# zero_board.net
KiCad netlist of a schematic drawn in EAGLE
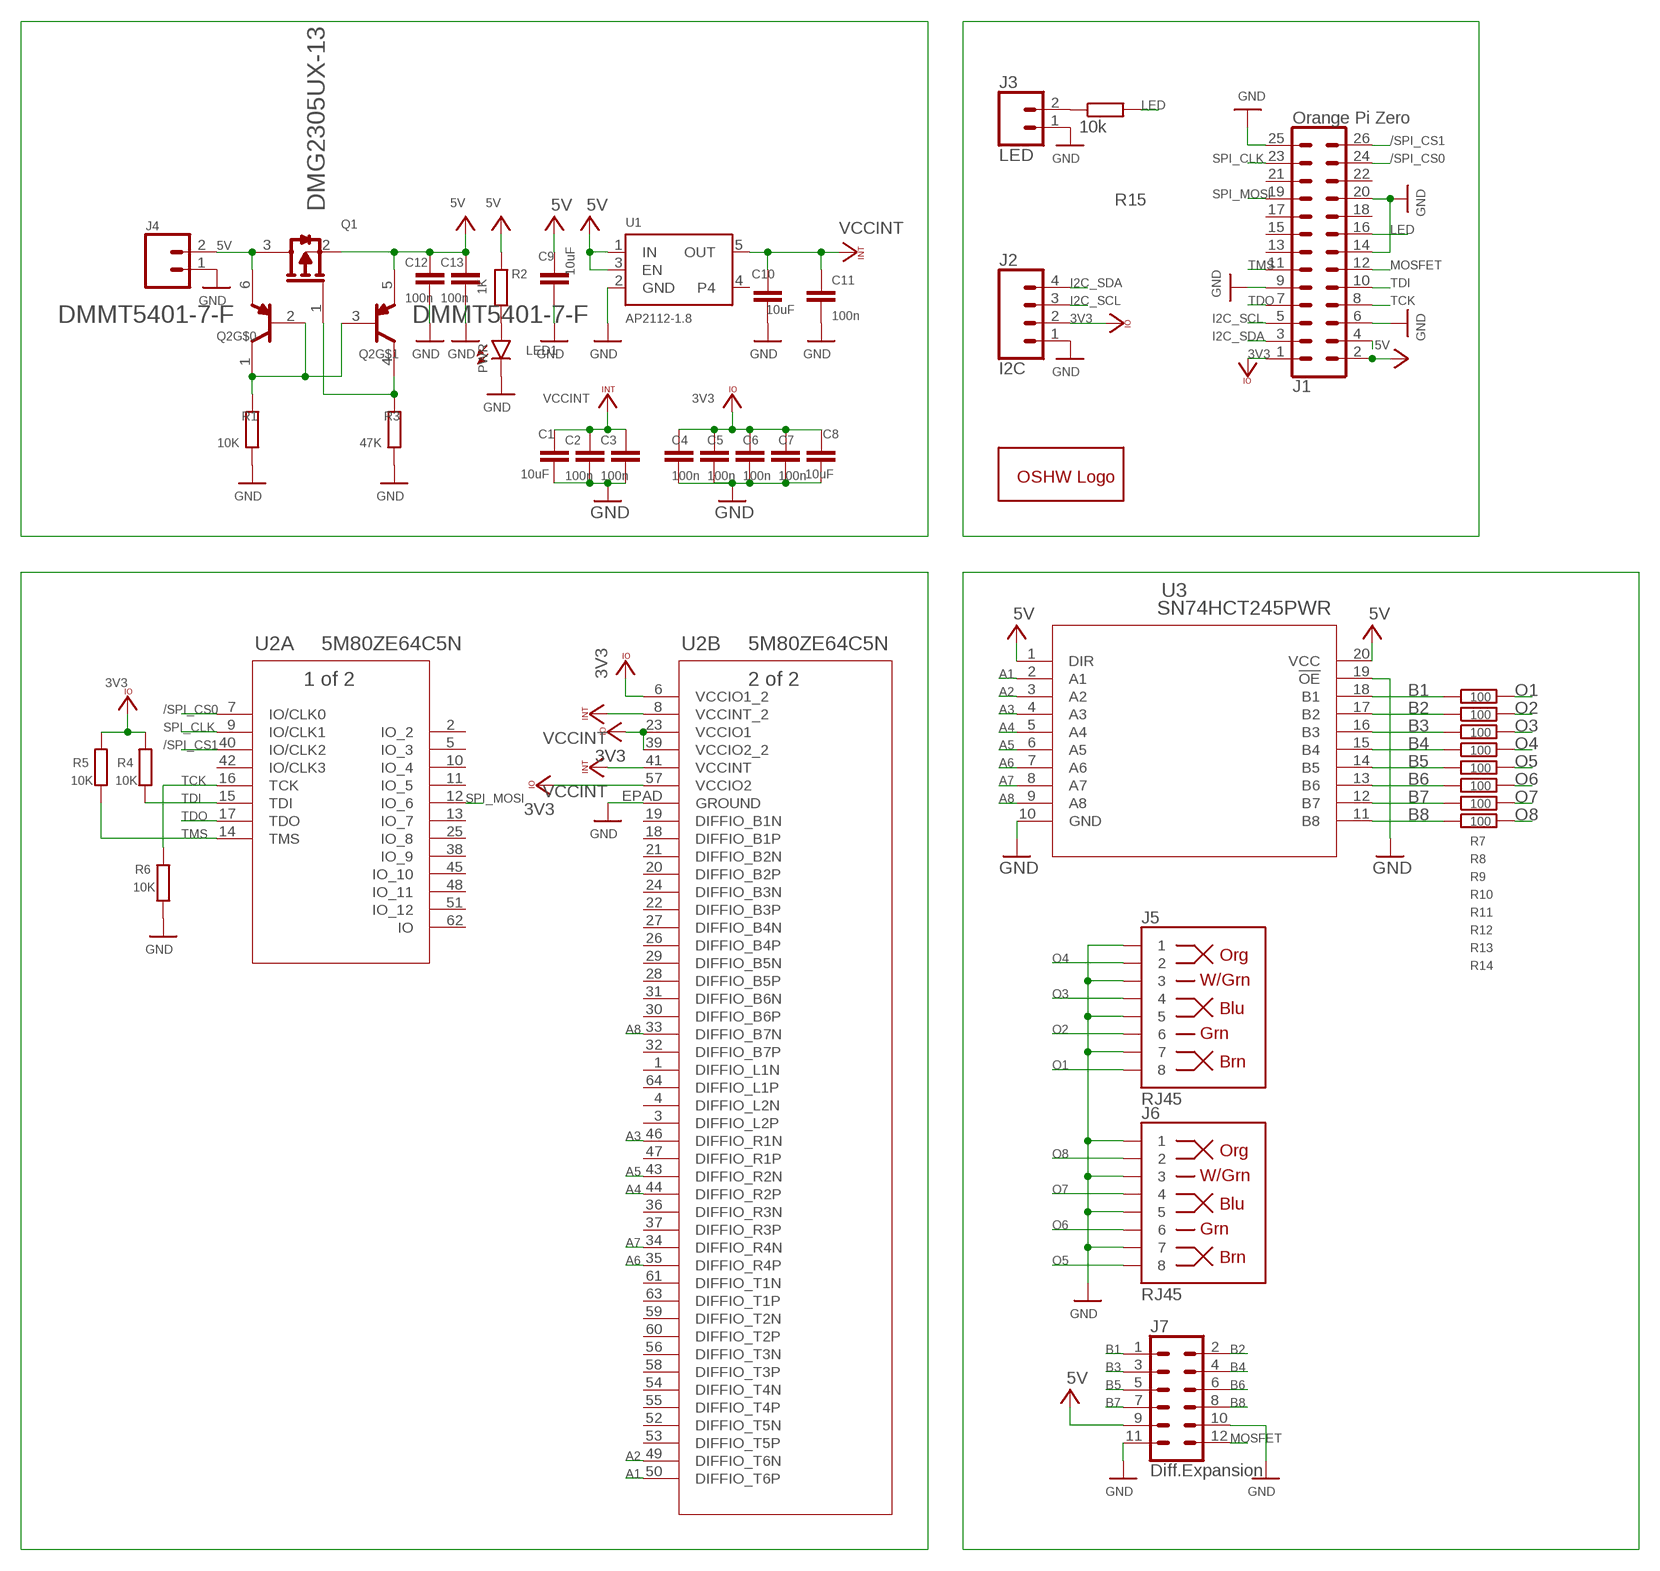
[diagram p0: schematic, sheet 1]

(export (version "E")
  (design (tool "Eeschema 10.0.6"))
  (components
    (comp (ref "C1")
      (value "10uF")
      (footprint "eagle-import:C0805")
      (libsource (lib "eagle-import") (part "C-EUC0805"))
    )
    (comp (ref "C2")
      (value "100n")
      (footprint "eagle-import:C0603")
      (libsource (lib "eagle-import") (part "C-EUC0603"))
    )
    (comp (ref "C3")
      (value "100n")
      (footprint "eagle-import:C0603")
      (libsource (lib "eagle-import") (part "C-EUC0603"))
    )
    (comp (ref "C4")
      (value "100n")
      (footprint "eagle-import:C0603")
      (libsource (lib "eagle-import") (part "C-EUC0603"))
    )
    (comp (ref "C5")
      (value "100n")
      (footprint "eagle-import:C0603")
      (libsource (lib "eagle-import") (part "C-EUC0603"))
    )
    (comp (ref "C6")
      (value "100n")
      (footprint "eagle-import:C0603")
      (libsource (lib "eagle-import") (part "C-EUC0603"))
    )
    (comp (ref "C7")
      (value "100n")
      (footprint "eagle-import:C0603")
      (libsource (lib "eagle-import") (part "C-EUC0603"))
    )
    (comp (ref "C8")
      (value "10uF")
      (footprint "eagle-import:C0805")
      (libsource (lib "eagle-import") (part "C-EUC0805"))
    )
    (comp (ref "C9")
      (value "10uF")
      (footprint "eagle-import:C0805")
      (libsource (lib "eagle-import") (part "C-EUC0805"))
    )
    (comp (ref "C10")
      (value "10uF")
      (footprint "eagle-import:C0805")
      (libsource (lib "eagle-import") (part "C-EUC0805"))
    )
    (comp (ref "C11")
      (value "100n")
      (footprint "eagle-import:C0603")
      (libsource (lib "eagle-import") (part "C-EUC0603"))
    )
    (comp (ref "C12")
      (value "100n")
      (footprint "eagle-import:C0603")
      (libsource (lib "eagle-import") (part "C-EUC0603"))
    )
    (comp (ref "C13")
      (value "100n")
      (footprint "eagle-import:C0603")
      (libsource (lib "eagle-import") (part "C-EUC0603"))
    )
    (comp (ref "GOLD_ORB_SM1")
      (value "OSHWLOGOLOGO5MM")
      (footprint "eagle-import:OSHW_5MM")
      (libsource (lib "eagle-import") (part "OSHWLOGOLOGO5MM"))
    )
    (comp (ref "J1")
      (value "Orange Pi Zero")
      (footprint "eagle-import:2X13")
      (libsource (lib "eagle-import") (part "CONN_13X22X13"))
    )
    (comp (ref "J2")
      (value "I2C")
      (footprint "eagle-import:1X04")
      (libsource (lib "eagle-import") (part "CONN_04"))
    )
    (comp (ref "J3")
      (value "LED")
      (footprint "eagle-import:1X02")
      (libsource (lib "eagle-import") (part "SparkFun-Connectors_513_CONN_02"))
    )
    (comp (ref "J4")
      (value "5V")
      (footprint "eagle-import:SCREWTERMINAL-3.5MM-2")
      (libsource (lib "eagle-import") (part "CONN_023.5MM"))
    )
    (comp (ref "J5")
      (value "RJ45")
      (footprint "eagle-import:RJ45-8")
      (libsource (lib "eagle-import") (part "RJ45-8"))
    )
    (comp (ref "J6")
      (value "RJ45")
      (footprint "eagle-import:RJ45-8")
      (libsource (lib "eagle-import") (part "RJ45-8"))
    )
    (comp (ref "J7")
      (value "Diff.Expansion")
      (footprint "eagle-import:2X6")
      (libsource (lib "eagle-import") (part "CONN_06X2PTH_FEMALE"))
    )
    (comp (ref "LED1")
      (value "PWR")
      (footprint "eagle-import:CHIP-LED0603")
      (libsource (lib "eagle-import") (part "LEDCHIP-LED0603"))
    )
    (comp (ref "Q1")
      (value "DIODES_INC._DMG2305UX-13DIODES_INC._DMG2305UX-13_0_0")
      (footprint "eagle-import:DIODES_INC._DMG2305UX-13_0")
      (fields
        (field (name "DIGIKEY_PART_NUMBER") "DMG2305UX-13DICT-ND")
        (field (name "MF") "Diodes Inc.")
        (field (name "MOUSER_PART_NUMBER") "621-DMG2305UX-13")
      )
      (libsource (lib "eagle-import") (part "DIODES_INC._DMG2305UX-13DIODES_INC._DMG2305UX-13_0_0"))
    )
    (comp (ref "Q2")
      (value "DMMT5401-7-F_0_0")
      (footprint "eagle-import:DIODES_DMMT5401-7-F_0")
      (fields
        (field (name "DIGIKEY_PART_NUMBER") "DMMT5401-FDICT-ND")
        (field (name "MF") "Diodes")
        (field (name "MOUSER_PART_NUMBER") "621-DMMT5401-7-F")
      )
      (libsource (lib "eagle-import") (part "DIODES_DMMT5401-7-FDIODES_DMMT5401-7-F_0_0"))
    )
    (comp (ref "R1")
      (value "10K")
      (footprint "eagle-import:R0402")
      (libsource (lib "eagle-import") (part "R-EU_R0402"))
    )
    (comp (ref "R2")
      (value "1K")
      (footprint "eagle-import:R0402")
      (libsource (lib "eagle-import") (part "resistor_348_R-EU_R0402"))
    )
    (comp (ref "R3")
      (value "47K")
      (footprint "eagle-import:R0402")
      (libsource (lib "eagle-import") (part "R-EU_R0402"))
    )
    (comp (ref "R4")
      (value "10K")
      (footprint "eagle-import:R0402")
      (libsource (lib "eagle-import") (part "R-EU_R0402"))
    )
    (comp (ref "R5")
      (value "10K")
      (footprint "eagle-import:R0402")
      (libsource (lib "eagle-import") (part "R-EU_R0402"))
    )
    (comp (ref "R6")
      (value "10K")
      (footprint "eagle-import:R0402")
      (libsource (lib "eagle-import") (part "R-EU_R0402"))
    )
    (comp (ref "R7")
      (value "100")
      (footprint "eagle-import:R0402")
      (libsource (lib "eagle-import") (part "R-EU_R0402"))
    )
    (comp (ref "R8")
      (value "100")
      (footprint "eagle-import:R0402")
      (libsource (lib "eagle-import") (part "R-EU_R0402"))
    )
    (comp (ref "R9")
      (value "100")
      (footprint "eagle-import:R0402")
      (libsource (lib "eagle-import") (part "R-EU_R0402"))
    )
    (comp (ref "R10")
      (value "100")
      (footprint "eagle-import:R0402")
      (libsource (lib "eagle-import") (part "R-EU_R0402"))
    )
    (comp (ref "R11")
      (value "100")
      (footprint "eagle-import:R0402")
      (libsource (lib "eagle-import") (part "R-EU_R0402"))
    )
    (comp (ref "R12")
      (value "100")
      (footprint "eagle-import:R0402")
      (libsource (lib "eagle-import") (part "R-EU_R0402"))
    )
    (comp (ref "R13")
      (value "100")
      (footprint "eagle-import:R0402")
      (libsource (lib "eagle-import") (part "R-EU_R0402"))
    )
    (comp (ref "R14")
      (value "100")
      (footprint "eagle-import:R0402")
      (libsource (lib "eagle-import") (part "R-EU_R0402"))
    )
    (comp (ref "R15")
      (value "10k")
      (footprint "eagle-import:R0402")
      (libsource (lib "eagle-import") (part "R-EU_R0402"))
    )
    (comp (ref "U1")
      (value "AP2112-1.8")
      (footprint "eagle-import:SOT23-5")
      (libsource (lib "eagle-import") (part "VREG_SOT23-5"))
    )
    (comp (ref "U2")
      (value "5M80ZE64C5N")
      (footprint "eagle-import:EQFP64P_A1P2-D4P5_INT-L")
      (fields (field (name "COPYRIGHT") "Copyright (C) 2018 Accelerated Designs. All rights reserved"))
      (libsource (lib "eagle-import") (part "5M80ZE64C5NEQFP64P_A1P2-D4P5_INT-L"))
    )
    (comp (ref "U3")
      (value "SN74HCT245PWR")
      (footprint "eagle-import:PW20")
      (fields
        (field (name "GENERIC_PART_NUMBER") "SN74HCT245")
        (field (name "MANUFACTURER") "Texas Instruments")
      )
      (libsource (lib "eagle-import") (part "SN74HCT245PWR"))
    )
  )
  (nets
    (net (code "1") (name "/A1") (class "Default")
      (node (ref "U2") (pin "50") (pinfunction "DIFFIO_T6P_50") (pintype "bidirectional"))
      (node (ref "U3") (pin "2") (pinfunction "A1_2") (pintype "bidirectional"))
    )
    (net (code "2") (name "/A2") (class "Default")
      (node (ref "U2") (pin "49") (pinfunction "DIFFIO_T6N_49") (pintype "bidirectional"))
      (node (ref "U3") (pin "3") (pinfunction "A2_3") (pintype "bidirectional"))
    )
    (net (code "3") (name "/A3") (class "Default")
      (node (ref "U2") (pin "46") (pinfunction "DIFFIO_R1N_46") (pintype "bidirectional"))
      (node (ref "U3") (pin "4") (pinfunction "A3_4") (pintype "bidirectional"))
    )
    (net (code "4") (name "/A4") (class "Default")
      (node (ref "U2") (pin "44") (pinfunction "DIFFIO_R2P_44") (pintype "bidirectional"))
      (node (ref "U3") (pin "5") (pinfunction "A4_5") (pintype "bidirectional"))
    )
    (net (code "5") (name "/A5") (class "Default")
      (node (ref "U2") (pin "43") (pinfunction "DIFFIO_R2N_43") (pintype "bidirectional"))
      (node (ref "U3") (pin "6") (pinfunction "A5_6") (pintype "bidirectional"))
    )
    (net (code "6") (name "/A6") (class "Default")
      (node (ref "U2") (pin "35") (pinfunction "DIFFIO_R4P_35") (pintype "bidirectional"))
      (node (ref "U3") (pin "7") (pinfunction "A6_7") (pintype "bidirectional"))
    )
    (net (code "7") (name "/A7") (class "Default")
      (node (ref "U2") (pin "34") (pinfunction "DIFFIO_R4N_34") (pintype "bidirectional"))
      (node (ref "U3") (pin "8") (pinfunction "A7_8") (pintype "bidirectional"))
    )
    (net (code "8") (name "/A8") (class "Default")
      (node (ref "U2") (pin "33") (pinfunction "DIFFIO_B7N_33") (pintype "bidirectional"))
      (node (ref "U3") (pin "9") (pinfunction "A8_9") (pintype "bidirectional"))
    )
    (net (code "9") (name "/B1") (class "Default")
      (node (ref "J7") (pin "1") (pinfunction "1_1") (pintype "passive"))
      (node (ref "R7") (pin "1") (pinfunction "1_1") (pintype "passive"))
      (node (ref "U3") (pin "18") (pinfunction "B1_18") (pintype "bidirectional"))
    )
    (net (code "10") (name "/B2") (class "Default")
      (node (ref "J7") (pin "2") (pinfunction "2_2") (pintype "passive"))
      (node (ref "R8") (pin "1") (pinfunction "1_1") (pintype "passive"))
      (node (ref "U3") (pin "17") (pinfunction "B2_17") (pintype "bidirectional"))
    )
    (net (code "11") (name "/B3") (class "Default")
      (node (ref "J7") (pin "3") (pinfunction "3_3") (pintype "passive"))
      (node (ref "R9") (pin "1") (pinfunction "1_1") (pintype "passive"))
      (node (ref "U3") (pin "16") (pinfunction "B3_16") (pintype "bidirectional"))
    )
    (net (code "12") (name "/B4") (class "Default")
      (node (ref "J7") (pin "4") (pinfunction "4_4") (pintype "passive"))
      (node (ref "R10") (pin "1") (pinfunction "1_1") (pintype "passive"))
      (node (ref "U3") (pin "15") (pinfunction "B4_15") (pintype "bidirectional"))
    )
    (net (code "13") (name "/B5") (class "Default")
      (node (ref "J7") (pin "5") (pinfunction "5_5") (pintype "passive"))
      (node (ref "R11") (pin "1") (pinfunction "1_1") (pintype "passive"))
      (node (ref "U3") (pin "14") (pinfunction "B5_14") (pintype "bidirectional"))
    )
    (net (code "14") (name "/B6") (class "Default")
      (node (ref "J7") (pin "6") (pinfunction "6_6") (pintype "passive"))
      (node (ref "R12") (pin "1") (pinfunction "1_1") (pintype "passive"))
      (node (ref "U3") (pin "13") (pinfunction "B6_13") (pintype "bidirectional"))
    )
    (net (code "15") (name "/B7") (class "Default")
      (node (ref "J7") (pin "7") (pinfunction "7_7") (pintype "passive"))
      (node (ref "R13") (pin "1") (pinfunction "1_1") (pintype "passive"))
      (node (ref "U3") (pin "12") (pinfunction "B7_12") (pintype "bidirectional"))
    )
    (net (code "16") (name "/B8") (class "Default")
      (node (ref "J7") (pin "8") (pinfunction "8_8") (pintype "passive"))
      (node (ref "R14") (pin "1") (pinfunction "1_1") (pintype "passive"))
      (node (ref "U3") (pin "11") (pinfunction "B8_11") (pintype "bidirectional"))
    )
    (net (code "17") (name "/I2C_SCL") (class "Default")
      (node (ref "J1") (pin "5") (pinfunction "5_5") (pintype "passive"))
      (node (ref "J2") (pin "3") (pinfunction "3_3") (pintype "passive"))
    )
    (net (code "18") (name "/I2C_SDA") (class "Default")
      (node (ref "J1") (pin "3") (pinfunction "3_3") (pintype "passive"))
      (node (ref "J2") (pin "4") (pinfunction "4_4") (pintype "passive"))
    )
    (net (code "19") (name "/LED") (class "Default")
      (node (ref "J1") (pin "16") (pinfunction "16_16") (pintype "passive"))
      (node (ref "R15") (pin "2") (pinfunction "2_2") (pintype "passive"))
    )
    (net (code "20") (name "/MOSFET") (class "Default")
      (node (ref "J1") (pin "12") (pinfunction "12_12") (pintype "passive"))
      (node (ref "J7") (pin "12") (pinfunction "12_12") (pintype "passive"))
    )
    (net (code "21") (name "/O1") (class "Default")
      (node (ref "J5") (pin "8") (pinfunction "8_8") (pintype "bidirectional"))
      (node (ref "R7") (pin "2") (pinfunction "2_2") (pintype "passive"))
    )
    (net (code "22") (name "/O2") (class "Default")
      (node (ref "J5") (pin "6") (pinfunction "6_6") (pintype "bidirectional"))
      (node (ref "R8") (pin "2") (pinfunction "2_2") (pintype "passive"))
    )
    (net (code "23") (name "/O3") (class "Default")
      (node (ref "J5") (pin "4") (pinfunction "4_4") (pintype "bidirectional"))
      (node (ref "R9") (pin "2") (pinfunction "2_2") (pintype "passive"))
    )
    (net (code "24") (name "/O4") (class "Default")
      (node (ref "J5") (pin "2") (pinfunction "2_2") (pintype "bidirectional"))
      (node (ref "R10") (pin "2") (pinfunction "2_2") (pintype "passive"))
    )
    (net (code "25") (name "/O5") (class "Default")
      (node (ref "J6") (pin "8") (pinfunction "8_8") (pintype "bidirectional"))
      (node (ref "R11") (pin "2") (pinfunction "2_2") (pintype "passive"))
    )
    (net (code "26") (name "/O6") (class "Default")
      (node (ref "J6") (pin "6") (pinfunction "6_6") (pintype "bidirectional"))
      (node (ref "R12") (pin "2") (pinfunction "2_2") (pintype "passive"))
    )
    (net (code "27") (name "/O7") (class "Default")
      (node (ref "J6") (pin "4") (pinfunction "4_4") (pintype "bidirectional"))
      (node (ref "R13") (pin "2") (pinfunction "2_2") (pintype "passive"))
    )
    (net (code "28") (name "/O8") (class "Default")
      (node (ref "J6") (pin "2") (pinfunction "2_2") (pintype "bidirectional"))
      (node (ref "R14") (pin "2") (pinfunction "2_2") (pintype "passive"))
    )
    (net (code "29") (name "/SPI_CLK") (class "Default")
      (node (ref "J1") (pin "23") (pinfunction "23_23") (pintype "passive"))
      (node (ref "U2") (pin "9") (pinfunction "IO/CLK1_9") (pintype "bidirectional"))
    )
    (net (code "30") (name "/SPI_MOSI") (class "Default")
      (node (ref "J1") (pin "19") (pinfunction "19_19") (pintype "passive"))
      (node (ref "U2") (pin "12") (pinfunction "IO_6_12") (pintype "bidirectional"))
    )
    (net (code "31") (name "/TCK") (class "Default")
      (node (ref "J1") (pin "8") (pinfunction "8_8") (pintype "passive"))
      (node (ref "R6") (pin "2") (pinfunction "2_2") (pintype "passive"))
      (node (ref "U2") (pin "16") (pinfunction "TCK_16") (pintype "passive"))
    )
    (net (code "32") (name "/TDI") (class "Default")
      (node (ref "J1") (pin "10") (pinfunction "10_10") (pintype "passive"))
      (node (ref "R4") (pin "1") (pinfunction "1_1") (pintype "passive"))
      (node (ref "U2") (pin "15") (pinfunction "TDI_15") (pintype "passive"))
    )
    (net (code "33") (name "/TDO") (class "Default")
      (node (ref "J1") (pin "7") (pinfunction "7_7") (pintype "passive"))
      (node (ref "U2") (pin "17") (pinfunction "TDO_17") (pintype "passive"))
    )
    (net (code "34") (name "/TMS") (class "Default")
      (node (ref "J1") (pin "11") (pinfunction "11_11") (pintype "passive"))
      (node (ref "R5") (pin "1") (pinfunction "1_1") (pintype "passive"))
      (node (ref "U2") (pin "14") (pinfunction "TMS_14") (pintype "passive"))
    )
    (net (code "35") (name "/{slash}SPI_CS0") (class "Default")
      (node (ref "J1") (pin "24") (pinfunction "24_24") (pintype "passive"))
      (node (ref "U2") (pin "7") (pinfunction "IO/CLK0_7") (pintype "bidirectional"))
    )
    (net (code "36") (name "/{slash}SPI_CS1") (class "Default")
      (node (ref "J1") (pin "26") (pinfunction "26_26") (pintype "passive"))
      (node (ref "U2") (pin "40") (pinfunction "IO/CLK2_40") (pintype "bidirectional"))
    )
    (net (code "37") (name "3V3") (class "Default")
      (node (ref "C4") (pin "1") (pinfunction "1_1") (pintype "passive"))
      (node (ref "C5") (pin "1") (pinfunction "1_1") (pintype "passive"))
      (node (ref "C6") (pin "1") (pinfunction "1_1") (pintype "passive"))
      (node (ref "C7") (pin "1") (pinfunction "1_1") (pintype "passive"))
      (node (ref "C8") (pin "1") (pinfunction "1_1") (pintype "passive"))
      (node (ref "J1") (pin "1") (pinfunction "1_1") (pintype "passive"))
      (node (ref "J2") (pin "2") (pinfunction "2_2") (pintype "passive"))
      (node (ref "R4") (pin "2") (pinfunction "2_2") (pintype "passive"))
      (node (ref "R5") (pin "2") (pinfunction "2_2") (pintype "passive"))
      (node (ref "U2") (pin "23") (pinfunction "VCCIO1_23") (pintype "power_in"))
      (node (ref "U2") (pin "39") (pinfunction "VCCIO2_2_39") (pintype "power_in"))
      (node (ref "U2") (pin "57") (pinfunction "VCCIO2_57") (pintype "power_in"))
      (node (ref "U2") (pin "6") (pinfunction "VCCIO1_2_6") (pintype "power_in"))
    )
    (net (code "38") (name "5V") (class "Default")
      (node (ref "C12") (pin "1") (pinfunction "1_1") (pintype "passive"))
      (node (ref "C13") (pin "1") (pinfunction "1_1") (pintype "passive"))
      (node (ref "C9") (pin "1") (pinfunction "1_1") (pintype "passive"))
      (node (ref "J1") (pin "2") (pinfunction "2_2") (pintype "passive"))
      (node (ref "J7") (pin "9") (pinfunction "9_9") (pintype "passive"))
      (node (ref "Q1") (pin "2") (pinfunction "S_2") (pintype "passive"))
      (node (ref "Q2") (pin "5") (pinfunction "E2_5") (pintype "passive"))
      (node (ref "R2") (pin "1") (pinfunction "1_1") (pintype "passive"))
      (node (ref "U1") (pin "1") (pinfunction "IN_1") (pintype "power_in"))
      (node (ref "U1") (pin "3") (pinfunction "EN_3") (pintype "input"))
      (node (ref "U3") (pin "1") (pinfunction "DIR_1") (pintype "input"))
      (node (ref "U3") (pin "20") (pinfunction "VCC_20") (pintype "power_in"))
    )
    (net (code "39") (name "GND") (class "Default")
      (node (ref "C1") (pin "2") (pinfunction "2_2") (pintype "passive"))
      (node (ref "C10") (pin "2") (pinfunction "2_2") (pintype "passive"))
      (node (ref "C11") (pin "2") (pinfunction "2_2") (pintype "passive"))
      (node (ref "C12") (pin "2") (pinfunction "2_2") (pintype "passive"))
      (node (ref "C13") (pin "2") (pinfunction "2_2") (pintype "passive"))
      (node (ref "C2") (pin "2") (pinfunction "2_2") (pintype "passive"))
      (node (ref "C3") (pin "2") (pinfunction "2_2") (pintype "passive"))
      (node (ref "C4") (pin "2") (pinfunction "2_2") (pintype "passive"))
      (node (ref "C5") (pin "2") (pinfunction "2_2") (pintype "passive"))
      (node (ref "C6") (pin "2") (pinfunction "2_2") (pintype "passive"))
      (node (ref "C7") (pin "2") (pinfunction "2_2") (pintype "passive"))
      (node (ref "C8") (pin "2") (pinfunction "2_2") (pintype "passive"))
      (node (ref "C9") (pin "2") (pinfunction "2_2") (pintype "passive"))
      (node (ref "J1") (pin "14") (pinfunction "14_14") (pintype "passive"))
      (node (ref "J1") (pin "20") (pinfunction "20_20") (pintype "passive"))
      (node (ref "J1") (pin "25") (pinfunction "25_25") (pintype "passive"))
      (node (ref "J1") (pin "6") (pinfunction "6_6") (pintype "passive"))
      (node (ref "J1") (pin "9") (pinfunction "9_9") (pintype "passive"))
      (node (ref "J2") (pin "1") (pinfunction "1_1") (pintype "passive"))
      (node (ref "J3") (pin "1") (pinfunction "1_1") (pintype "passive"))
      (node (ref "J4") (pin "1") (pinfunction "1_1") (pintype "passive"))
      (node (ref "J5") (pin "1") (pinfunction "1_1") (pintype "bidirectional"))
      (node (ref "J5") (pin "3") (pinfunction "3_3") (pintype "bidirectional"))
      (node (ref "J5") (pin "5") (pinfunction "5_5") (pintype "bidirectional"))
      (node (ref "J5") (pin "7") (pinfunction "7_7") (pintype "bidirectional"))
      (node (ref "J6") (pin "1") (pinfunction "1_1") (pintype "bidirectional"))
      (node (ref "J6") (pin "3") (pinfunction "3_3") (pintype "bidirectional"))
      (node (ref "J6") (pin "5") (pinfunction "5_5") (pintype "bidirectional"))
      (node (ref "J6") (pin "7") (pinfunction "7_7") (pintype "bidirectional"))
      (node (ref "J7") (pin "10") (pinfunction "10_10") (pintype "passive"))
      (node (ref "J7") (pin "11") (pinfunction "11_11") (pintype "passive"))
      (node (ref "LED1") (pin "C") (pinfunction "C_C") (pintype "passive"))
      (node (ref "R1") (pin "1") (pinfunction "1_1") (pintype "passive"))
      (node (ref "R3") (pin "1") (pinfunction "1_1") (pintype "passive"))
      (node (ref "R6") (pin "1") (pinfunction "1_1") (pintype "passive"))
      (node (ref "U1") (pin "2") (pinfunction "GND_2") (pintype "power_in"))
      (node (ref "U2") (pin "EPAD") (pinfunction "GROUND_EPAD") (pintype "passive"))
      (node (ref "U3") (pin "10") (pinfunction "GND_10") (pintype "power_in"))
      (node (ref "U3") (pin "19") (pinfunction "~{OE}_19") (pintype "input"))
    )
    (net (code "40") (name "Net-(J3-Pad2)") (class "Default")
      (node (ref "J3") (pin "2") (pinfunction "2_2") (pintype "passive"))
      (node (ref "R15") (pin "1") (pinfunction "1_1") (pintype "passive"))
    )
    (net (code "41") (name "Net-(LED1-PadA)") (class "Default")
      (node (ref "LED1") (pin "A") (pinfunction "A_A") (pintype "passive"))
      (node (ref "R2") (pin "2") (pinfunction "2_2") (pintype "passive"))
    )
    (net (code "42") (name "Net-(Q1-D)") (class "Default")
      (node (ref "J4") (pin "2") (pinfunction "2_2") (pintype "passive"))
      (node (ref "Q1") (pin "3") (pinfunction "D_3") (pintype "passive"))
      (node (ref "Q2") (pin "6") (pinfunction "E1_6") (pintype "passive"))
    )
    (net (code "43") (name "Net-(Q1-G)") (class "Default")
      (node (ref "Q1") (pin "1") (pinfunction "G_1") (pintype "passive"))
      (node (ref "Q2") (pin "4") (pinfunction "C2_4") (pintype "passive"))
      (node (ref "R3") (pin "2") (pinfunction "2_2") (pintype "passive"))
    )
    (net (code "44") (name "Net-(Q2A-B1)") (class "Default")
      (node (ref "Q2") (pin "1") (pinfunction "C1_1") (pintype "passive"))
      (node (ref "Q2") (pin "2") (pinfunction "B1_2") (pintype "passive"))
      (node (ref "Q2") (pin "3") (pinfunction "B2_3") (pintype "passive"))
      (node (ref "R1") (pin "2") (pinfunction "2_2") (pintype "passive"))
    )
    (net (code "45") (name "VCCINT") (class "Default")
      (node (ref "C1") (pin "1") (pinfunction "1_1") (pintype "passive"))
      (node (ref "C10") (pin "1") (pinfunction "1_1") (pintype "passive"))
      (node (ref "C11") (pin "1") (pinfunction "1_1") (pintype "passive"))
      (node (ref "C2") (pin "1") (pinfunction "1_1") (pintype "passive"))
      (node (ref "C3") (pin "1") (pinfunction "1_1") (pintype "passive"))
      (node (ref "U1") (pin "5") (pinfunction "OUT_5") (pintype "power_in"))
      (node (ref "U2") (pin "41") (pinfunction "VCCINT_41") (pintype "power_in"))
      (node (ref "U2") (pin "8") (pinfunction "VCCINT_2_8") (pintype "power_in"))
    )
    (net (code "46") (name "unconnected-(J1-Pad4)") (class "Default")
      (node (ref "J1") (pin "4") (pinfunction "4_4") (pintype "passive"))
    )
    (net (code "47") (name "unconnected-(J1-Pad13)") (class "Default")
      (node (ref "J1") (pin "13") (pinfunction "13_13") (pintype "passive"))
    )
    (net (code "48") (name "unconnected-(J1-Pad15)") (class "Default")
      (node (ref "J1") (pin "15") (pinfunction "15_15") (pintype "passive"))
    )
    (net (code "49") (name "unconnected-(J1-Pad17)") (class "Default")
      (node (ref "J1") (pin "17") (pinfunction "17_17") (pintype "passive"))
    )
    (net (code "50") (name "unconnected-(J1-Pad18)") (class "Default")
      (node (ref "J1") (pin "18") (pinfunction "18_18") (pintype "passive"))
    )
    (net (code "51") (name "unconnected-(J1-Pad21)") (class "Default")
      (node (ref "J1") (pin "21") (pinfunction "21_21") (pintype "passive"))
    )
    (net (code "52") (name "unconnected-(J1-Pad22)") (class "Default")
      (node (ref "J1") (pin "22") (pinfunction "22_22") (pintype "passive"))
    )
    (net (code "53") (name "unconnected-(U1-P4-Pad4)") (class "Default")
      (node (ref "U1") (pin "4") (pinfunction "P4_4") (pintype "bidirectional"))
    )
    (net (code "54") (name "unconnected-(U2A-IO-Pad62)") (class "Default")
      (node (ref "U2") (pin "62") (pinfunction "IO_62") (pintype "bidirectional"))
    )
    (net (code "55") (name "unconnected-(U2A-IO_2-Pad2)") (class "Default")
      (node (ref "U2") (pin "2") (pinfunction "IO_2_2") (pintype "bidirectional"))
    )
    (net (code "56") (name "unconnected-(U2A-IO_3-Pad5)") (class "Default")
      (node (ref "U2") (pin "5") (pinfunction "IO_3_5") (pintype "bidirectional"))
    )
    (net (code "57") (name "unconnected-(U2A-IO_4-Pad10)") (class "Default")
      (node (ref "U2") (pin "10") (pinfunction "IO_4_10") (pintype "bidirectional"))
    )
    (net (code "58") (name "unconnected-(U2A-IO_5-Pad11)") (class "Default")
      (node (ref "U2") (pin "11") (pinfunction "IO_5_11") (pintype "bidirectional"))
    )
    (net (code "59") (name "unconnected-(U2A-IO_7-Pad13)") (class "Default")
      (node (ref "U2") (pin "13") (pinfunction "IO_7_13") (pintype "bidirectional"))
    )
    (net (code "60") (name "unconnected-(U2A-IO_8-Pad25)") (class "Default")
      (node (ref "U2") (pin "25") (pinfunction "IO_8_25") (pintype "bidirectional"))
    )
    (net (code "61") (name "unconnected-(U2A-IO_9-Pad38)") (class "Default")
      (node (ref "U2") (pin "38") (pinfunction "IO_9_38") (pintype "bidirectional"))
    )
    (net (code "62") (name "unconnected-(U2A-IO_10-Pad45)") (class "Default")
      (node (ref "U2") (pin "45") (pinfunction "IO_10_45") (pintype "bidirectional"))
    )
    (net (code "63") (name "unconnected-(U2A-IO_11-Pad48)") (class "Default")
      (node (ref "U2") (pin "48") (pinfunction "IO_11_48") (pintype "bidirectional"))
    )
    (net (code "64") (name "unconnected-(U2A-IO_12-Pad51)") (class "Default")
      (node (ref "U2") (pin "51") (pinfunction "IO_12_51") (pintype "bidirectional"))
    )
    (net (code "65") (name "unconnected-(U2A-IO{slash}CLK3-Pad42)") (class "Default")
      (node (ref "U2") (pin "42") (pinfunction "IO/CLK3_42") (pintype "bidirectional"))
    )
    (net (code "66") (name "unconnected-(U2B-DIFFIO_B1N-Pad19)") (class "Default")
      (node (ref "U2") (pin "19") (pinfunction "DIFFIO_B1N_19") (pintype "bidirectional"))
    )
    (net (code "67") (name "unconnected-(U2B-DIFFIO_B1P-Pad18)") (class "Default")
      (node (ref "U2") (pin "18") (pinfunction "DIFFIO_B1P_18") (pintype "bidirectional"))
    )
    (net (code "68") (name "unconnected-(U2B-DIFFIO_B2N-Pad21)") (class "Default")
      (node (ref "U2") (pin "21") (pinfunction "DIFFIO_B2N_21") (pintype "bidirectional"))
    )
    (net (code "69") (name "unconnected-(U2B-DIFFIO_B2P-Pad20)") (class "Default")
      (node (ref "U2") (pin "20") (pinfunction "DIFFIO_B2P_20") (pintype "bidirectional"))
    )
    (net (code "70") (name "unconnected-(U2B-DIFFIO_B3N-Pad24)") (class "Default")
      (node (ref "U2") (pin "24") (pinfunction "DIFFIO_B3N_24") (pintype "bidirectional"))
    )
    (net (code "71") (name "unconnected-(U2B-DIFFIO_B3P-Pad22)") (class "Default")
      (node (ref "U2") (pin "22") (pinfunction "DIFFIO_B3P_22") (pintype "bidirectional"))
    )
    (net (code "72") (name "unconnected-(U2B-DIFFIO_B4N-Pad27)") (class "Default")
      (node (ref "U2") (pin "27") (pinfunction "DIFFIO_B4N_27") (pintype "bidirectional"))
    )
    (net (code "73") (name "unconnected-(U2B-DIFFIO_B4P-Pad26)") (class "Default")
      (node (ref "U2") (pin "26") (pinfunction "DIFFIO_B4P_26") (pintype "bidirectional"))
    )
    (net (code "74") (name "unconnected-(U2B-DIFFIO_B5N-Pad29)") (class "Default")
      (node (ref "U2") (pin "29") (pinfunction "DIFFIO_B5N_29") (pintype "bidirectional"))
    )
    (net (code "75") (name "unconnected-(U2B-DIFFIO_B5P-Pad28)") (class "Default")
      (node (ref "U2") (pin "28") (pinfunction "DIFFIO_B5P_28") (pintype "bidirectional"))
    )
    (net (code "76") (name "unconnected-(U2B-DIFFIO_B6N-Pad31)") (class "Default")
      (node (ref "U2") (pin "31") (pinfunction "DIFFIO_B6N_31") (pintype "bidirectional"))
    )
    (net (code "77") (name "unconnected-(U2B-DIFFIO_B6P-Pad30)") (class "Default")
      (node (ref "U2") (pin "30") (pinfunction "DIFFIO_B6P_30") (pintype "bidirectional"))
    )
    (net (code "78") (name "unconnected-(U2B-DIFFIO_B7P-Pad32)") (class "Default")
      (node (ref "U2") (pin "32") (pinfunction "DIFFIO_B7P_32") (pintype "bidirectional"))
    )
    (net (code "79") (name "unconnected-(U2B-DIFFIO_L1N-Pad1)") (class "Default")
      (node (ref "U2") (pin "1") (pinfunction "DIFFIO_L1N_1") (pintype "bidirectional"))
    )
    (net (code "80") (name "unconnected-(U2B-DIFFIO_L1P-Pad64)") (class "Default")
      (node (ref "U2") (pin "64") (pinfunction "DIFFIO_L1P_64") (pintype "bidirectional"))
    )
    (net (code "81") (name "unconnected-(U2B-DIFFIO_L2N-Pad4)") (class "Default")
      (node (ref "U2") (pin "4") (pinfunction "DIFFIO_L2N_4") (pintype "bidirectional"))
    )
    (net (code "82") (name "unconnected-(U2B-DIFFIO_L2P-Pad3)") (class "Default")
      (node (ref "U2") (pin "3") (pinfunction "DIFFIO_L2P_3") (pintype "bidirectional"))
    )
    (net (code "83") (name "unconnected-(U2B-DIFFIO_R1P-Pad47)") (class "Default")
      (node (ref "U2") (pin "47") (pinfunction "DIFFIO_R1P_47") (pintype "bidirectional"))
    )
    (net (code "84") (name "unconnected-(U2B-DIFFIO_R3N-Pad36)") (class "Default")
      (node (ref "U2") (pin "36") (pinfunction "DIFFIO_R3N_36") (pintype "bidirectional"))
    )
    (net (code "85") (name "unconnected-(U2B-DIFFIO_R3P-Pad37)") (class "Default")
      (node (ref "U2") (pin "37") (pinfunction "DIFFIO_R3P_37") (pintype "bidirectional"))
    )
    (net (code "86") (name "unconnected-(U2B-DIFFIO_T1N-Pad61)") (class "Default")
      (node (ref "U2") (pin "61") (pinfunction "DIFFIO_T1N_61") (pintype "bidirectional"))
    )
    (net (code "87") (name "unconnected-(U2B-DIFFIO_T1P-Pad63)") (class "Default")
      (node (ref "U2") (pin "63") (pinfunction "DIFFIO_T1P_63") (pintype "bidirectional"))
    )
    (net (code "88") (name "unconnected-(U2B-DIFFIO_T2N-Pad59)") (class "Default")
      (node (ref "U2") (pin "59") (pinfunction "DIFFIO_T2N_59") (pintype "bidirectional"))
    )
    (net (code "89") (name "unconnected-(U2B-DIFFIO_T2P-Pad60)") (class "Default")
      (node (ref "U2") (pin "60") (pinfunction "DIFFIO_T2P_60") (pintype "bidirectional"))
    )
    (net (code "90") (name "unconnected-(U2B-DIFFIO_T3N-Pad56)") (class "Default")
      (node (ref "U2") (pin "56") (pinfunction "DIFFIO_T3N_56") (pintype "bidirectional"))
    )
    (net (code "91") (name "unconnected-(U2B-DIFFIO_T3P-Pad58)") (class "Default")
      (node (ref "U2") (pin "58") (pinfunction "DIFFIO_T3P_58") (pintype "bidirectional"))
    )
    (net (code "92") (name "unconnected-(U2B-DIFFIO_T4N-Pad54)") (class "Default")
      (node (ref "U2") (pin "54") (pinfunction "DIFFIO_T4N_54") (pintype "bidirectional"))
    )
    (net (code "93") (name "unconnected-(U2B-DIFFIO_T4P-Pad55)") (class "Default")
      (node (ref "U2") (pin "55") (pinfunction "DIFFIO_T4P_55") (pintype "bidirectional"))
    )
    (net (code "94") (name "unconnected-(U2B-DIFFIO_T5N-Pad52)") (class "Default")
      (node (ref "U2") (pin "52") (pinfunction "DIFFIO_T5N_52") (pintype "bidirectional"))
    )
    (net (code "95") (name "unconnected-(U2B-DIFFIO_T5P-Pad53)") (class "Default")
      (node (ref "U2") (pin "53") (pinfunction "DIFFIO_T5P_53") (pintype "bidirectional"))
    )
  )
)
